# TalonSRXBreakout.net
KiCad netlist of a schematic drawn in Altium Designer
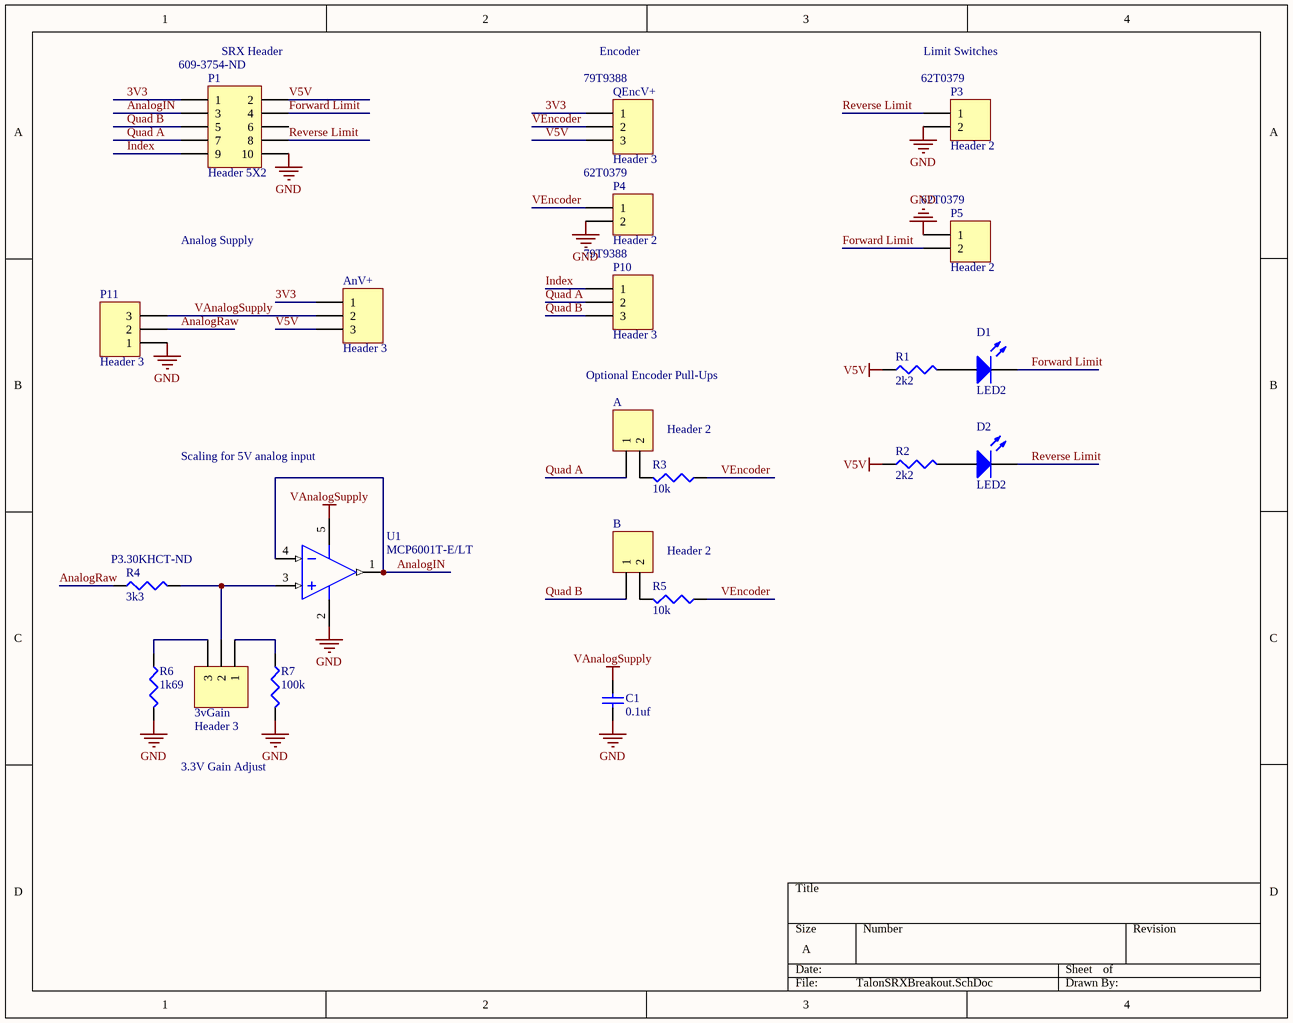
[diagram p0: TalonSRXBreakout.SchDoc]

(export (version "E")
  (design (tool "Eeschema 10.0.6"))
  (components
    (comp (ref "3vGain")
      (value "Header 3")
      (footprint "3 Pad Jumper")
      (description "Header, 3-Pin")
      (fields (field (name "PUBLISHER") "Electron"))
      (libsource (lib "") (part "Header 3_2"))
    )
    (comp (ref "A")
      (value "Header 2")
      (footprint "2 Pad Jumper")
      (description "Header, 2-Pin")
      (fields (field (name "PUBLISHER") "Electron"))
      (libsource (lib "Electron Custom Library") (part "Header 2"))
    )
    (comp (ref "AnV+")
      (value "Header 3")
      (footprint "3 Pad Jumper")
      (description "Header, 3-Pin")
      (fields (field (name "PUBLISHER") "Electron"))
      (libsource (lib "Electron Custom Library") (part "Header 3"))
    )
    (comp (ref "B")
      (value "Header 2")
      (footprint "2 Pad Jumper")
      (description "Header, 2-Pin")
      (fields (field (name "PUBLISHER") "Electron"))
      (libsource (lib "Electron Custom Library") (part "Header 2"))
    )
    (comp (ref "C1")
      (value "0.1uf")
      (footprint "CAP 0603 (1608)")
      (description "Capacitor Surface Mount")
      (libsource (lib "Electron Custom Library") (part "Capacitor Surface Mount"))
    )
    (comp (ref "D1")
      (value "LED2")
      (footprint "DIODE 0603/SOD-523F")
      (description "Typical RED, GREEN, YELLOW, AMBER GaAs LED")
      (fields (field (name "PUBLISHER") "Altium Limited"))
      (libsource (lib "Miscellaneous Devices") (part "LED2"))
    )
    (comp (ref "D2")
      (value "LED2")
      (footprint "DIODE 0603/SOD-523F")
      (description "Typical RED, GREEN, YELLOW, AMBER GaAs LED")
      (fields (field (name "PUBLISHER") "Altium Limited"))
      (libsource (lib "Miscellaneous Devices") (part "LED2"))
    )
    (comp (ref "P1")
      (value "Header 5X2")
      (footprint "HDR2X5 - 50Mil")
      (description "Header, 5-Pin, Dual row")
      (fields
        (field (name "SUPPLIER PART NUMBER 1") "609-3754-ND")
        (field (name "PUBLISHER") "Altium Limited")
      )
      (libsource (lib "Miscellaneous Connectors") (part "Header 5X2"))
    )
    (comp (ref "P3")
      (value "Header 2")
      (footprint "Wago 2 Pin")
      (description "Header, 2-Pin")
      (fields (field (name "SUPPLIER PART NUMBER 1") "62T0379") (field (name "PUBLISHER") "Altium Limited"))
      (libsource (lib "Miscellaneous Connectors") (part "Header 2"))
    )
    (comp (ref "P4")
      (value "Header 2")
      (footprint "Wago 2 Pin")
      (description "Header, 2-Pin")
      (fields (field (name "SUPPLIER PART NUMBER 1") "62T0379") (field (name "PUBLISHER") "Altium Limited"))
      (libsource (lib "Miscellaneous Connectors") (part "Header 2"))
    )
    (comp (ref "P5")
      (value "Header 2")
      (footprint "Wago 2 Pin")
      (description "Header, 2-Pin")
      (fields (field (name "SUPPLIER PART NUMBER 1") "62T0379") (field (name "PUBLISHER") "Altium Limited"))
      (libsource (lib "Miscellaneous Connectors") (part "Header 2"))
    )
    (comp (ref "P10")
      (value "Header 3")
      (footprint "Wago 3 Pin")
      (description "Header, 3-Pin")
      (fields (field (name "SUPPLIER PART NUMBER 1") "79T9388") (field (name "PUBLISHER") "Electron"))
      (libsource (lib "Electron Custom Library") (part "Header 3"))
    )
    (comp (ref "P11")
      (value "Header 3")
      (footprint "Wago 3 Pin")
      (description "Header, 3-Pin")
      (fields (field (name "PUBLISHER") "Electron"))
      (libsource (lib "") (part "Header 3_1"))
    )
    (comp (ref "QEncV+")
      (value "Header 3")
      (footprint "3 Pad Jumper")
      (description "Header, 3-Pin")
      (fields (field (name "SUPPLIER PART NUMBER 1") "79T9388") (field (name "PUBLISHER") "Electron"))
      (libsource (lib "Electron Custom Library") (part "Header 3"))
    )
    (comp (ref "R1")
      (value "2k2")
      (footprint "RES 0603 (1608)")
      (description "Resistor Surface Mount")
      (libsource (lib "Electron Custom Library") (part "Resistor Surface Mount"))
    )
    (comp (ref "R2")
      (value "2k2")
      (footprint "RES 0603 (1608)")
      (description "Resistor Surface Mount")
      (libsource (lib "Electron Custom Library") (part "Resistor Surface Mount"))
    )
    (comp (ref "R3")
      (value "10k")
      (footprint "RES 0603 (1608)")
      (description "Resistor Surface Mount")
      (libsource (lib "Electron Custom Library") (part "Resistor Surface Mount"))
    )
    (comp (ref "R4")
      (value "3k3")
      (footprint "RES 0603 (1608)")
      (description "Resistor Surface Mount")
      (fields (field (name "SUPPLIER PART NUMBER 2") "P3.30KHCT-ND"))
      (libsource (lib "Electron Custom Library") (part "Resistor Surface Mount"))
    )
    (comp (ref "R5")
      (value "10k")
      (footprint "RES 0603 (1608)")
      (description "Resistor Surface Mount")
      (libsource (lib "Electron Custom Library") (part "Resistor Surface Mount"))
    )
    (comp (ref "R6")
      (value "1k69")
      (footprint "RES 0603 (1608)")
      (description "Resistor Surface Mount")
      (libsource (lib "Electron Custom Library") (part "Resistor Surface Mount"))
    )
    (comp (ref "R7")
      (value "100k")
      (footprint "RES 0603 (1608)")
      (description "Resistor Surface Mount")
      (libsource (lib "Electron Custom Library") (part "Resistor Surface Mount"))
    )
    (comp (ref "U1")
      (value "MCP6001T-E/LT")
      (footprint "SC70-LT5_N")
      (description "1 MHz, Low-Power Operational Amplifier, 5-Pin SC-70, Extended Temperature, Tape and Reel")
      (fields (field (name "PUBLISHER") "Altium Limited"))
      (libsource (lib "Microchip Linear Devices") (part "MCP6001T-E/LT"))
    )
  )
  (nets
    (net (code "1") (name "/3V3") (class "Default")
      (node (ref "AnV+") (pin "1") (pinfunction "1_1") (pintype "passive"))
      (node (ref "P1") (pin "1") (pinfunction "1_1") (pintype "passive"))
      (node (ref "QEncV+") (pin "1") (pinfunction "1_1") (pintype "passive"))
    )
    (net (code "2") (name "/AnalogIN") (class "Default")
      (node (ref "P1") (pin "3") (pinfunction "3_3") (pintype "passive"))
      (node (ref "U1") (pin "1") (pinfunction "VOUT_1") (pintype "output"))
      (node (ref "U1") (pin "4") (pinfunction "VIN-_4") (pintype "input"))
    )
    (net (code "3") (name "/AnalogRaw") (class "Default")
      (node (ref "P11") (pin "2") (pinfunction "2_2") (pintype "passive"))
      (node (ref "R4") (pin "1") (pinfunction "1_1") (pintype "passive"))
    )
    (net (code "4") (name "/Forward Limit") (class "Default")
      (node (ref "D1") (pin "2") (pinfunction "K_2") (pintype "passive"))
      (node (ref "P1") (pin "4") (pinfunction "4_4") (pintype "passive"))
      (node (ref "P5") (pin "2") (pinfunction "2_2") (pintype "passive"))
    )
    (net (code "5") (name "/Index") (class "Default")
      (node (ref "P1") (pin "9") (pinfunction "9_9") (pintype "passive"))
      (node (ref "P10") (pin "1") (pinfunction "1_1") (pintype "passive"))
    )
    (net (code "6") (name "/Quad A") (class "Default")
      (node (ref "A") (pin "1") (pinfunction "1_1") (pintype "passive"))
      (node (ref "P1") (pin "7") (pinfunction "7_7") (pintype "passive"))
      (node (ref "P10") (pin "2") (pinfunction "2_2") (pintype "passive"))
    )
    (net (code "7") (name "/Quad B") (class "Default")
      (node (ref "B") (pin "1") (pinfunction "1_1") (pintype "passive"))
      (node (ref "P1") (pin "5") (pinfunction "5_5") (pintype "passive"))
      (node (ref "P10") (pin "3") (pinfunction "3_3") (pintype "passive"))
    )
    (net (code "8") (name "/Reverse Limit") (class "Default")
      (node (ref "D2") (pin "2") (pinfunction "K_2") (pintype "passive"))
      (node (ref "P1") (pin "8") (pinfunction "8_8") (pintype "passive"))
      (node (ref "P3") (pin "1") (pinfunction "1_1") (pintype "passive"))
    )
    (net (code "9") (name "/VEncoder") (class "Default")
      (node (ref "P4") (pin "1") (pinfunction "1_1") (pintype "passive"))
      (node (ref "QEncV+") (pin "2") (pinfunction "2_2") (pintype "passive"))
      (node (ref "R3") (pin "1") (pinfunction "1_1") (pintype "passive"))
      (node (ref "R5") (pin "1") (pinfunction "1_1") (pintype "passive"))
    )
    (net (code "10") (name "GND") (class "Default")
      (node (ref "C1") (pin "1") (pinfunction "1_1") (pintype "passive"))
      (node (ref "P1") (pin "10") (pinfunction "10_10") (pintype "passive"))
      (node (ref "P11") (pin "1") (pinfunction "1_1") (pintype "passive"))
      (node (ref "P3") (pin "2") (pinfunction "2_2") (pintype "passive"))
      (node (ref "P4") (pin "2") (pinfunction "2_2") (pintype "passive"))
      (node (ref "P5") (pin "1") (pinfunction "1_1") (pintype "passive"))
      (node (ref "R6") (pin "2") (pinfunction "2_2") (pintype "passive"))
      (node (ref "R7") (pin "2") (pinfunction "2_2") (pintype "passive"))
      (node (ref "U1") (pin "2") (pinfunction "VSS_2") (pintype "power_in"))
    )
    (net (code "11") (name "Net-(3vGain-Pad1)") (class "Default")
      (node (ref "3vGain") (pin "1") (pinfunction "1_1") (pintype "passive"))
      (node (ref "R7") (pin "1") (pinfunction "1_1") (pintype "passive"))
    )
    (net (code "12") (name "Net-(3vGain-Pad3)") (class "Default")
      (node (ref "3vGain") (pin "3") (pinfunction "3_3") (pintype "passive"))
      (node (ref "R6") (pin "1") (pinfunction "1_1") (pintype "passive"))
    )
    (net (code "13") (name "Net-(A-Pad2)") (class "Default")
      (node (ref "A") (pin "2") (pinfunction "2_2") (pintype "passive"))
      (node (ref "R3") (pin "2") (pinfunction "2_2") (pintype "passive"))
    )
    (net (code "14") (name "Net-(B-Pad2)") (class "Default")
      (node (ref "B") (pin "2") (pinfunction "2_2") (pintype "passive"))
      (node (ref "R5") (pin "2") (pinfunction "2_2") (pintype "passive"))
    )
    (net (code "15") (name "Net-(D1-A)") (class "Default")
      (node (ref "D1") (pin "1") (pinfunction "A_1") (pintype "passive"))
      (node (ref "R1") (pin "2") (pinfunction "2_2") (pintype "passive"))
    )
    (net (code "16") (name "Net-(D2-A)") (class "Default")
      (node (ref "D2") (pin "1") (pinfunction "A_1") (pintype "passive"))
      (node (ref "R2") (pin "2") (pinfunction "2_2") (pintype "passive"))
    )
    (net (code "17") (name "Net-(U1-VIN+)") (class "Default")
      (node (ref "3vGain") (pin "2") (pinfunction "2_2") (pintype "passive"))
      (node (ref "R4") (pin "2") (pinfunction "2_2") (pintype "passive"))
      (node (ref "U1") (pin "3") (pinfunction "VIN+_3") (pintype "input"))
    )
    (net (code "18") (name "V5V") (class "Default")
      (node (ref "AnV+") (pin "3") (pinfunction "3_3") (pintype "passive"))
      (node (ref "P1") (pin "2") (pinfunction "2_2") (pintype "passive"))
      (node (ref "QEncV+") (pin "3") (pinfunction "3_3") (pintype "passive"))
      (node (ref "R1") (pin "1") (pinfunction "1_1") (pintype "passive"))
      (node (ref "R2") (pin "1") (pinfunction "1_1") (pintype "passive"))
    )
    (net (code "19") (name "VAnalogSupply") (class "Default")
      (node (ref "AnV+") (pin "2") (pinfunction "2_2") (pintype "passive"))
      (node (ref "C1") (pin "2") (pinfunction "2_2") (pintype "passive"))
      (node (ref "P11") (pin "3") (pinfunction "3_3") (pintype "passive"))
      (node (ref "U1") (pin "5") (pinfunction "VDD_5") (pintype "power_in"))
    )
    (net (code "20") (name "unconnected-(P1-Pad6)") (class "Default")
      (node (ref "P1") (pin "6") (pinfunction "6_6") (pintype "passive"))
    )
  )
)
